# 03_RADIO.net
KiCad netlist of a schematic drawn in Altium Designer
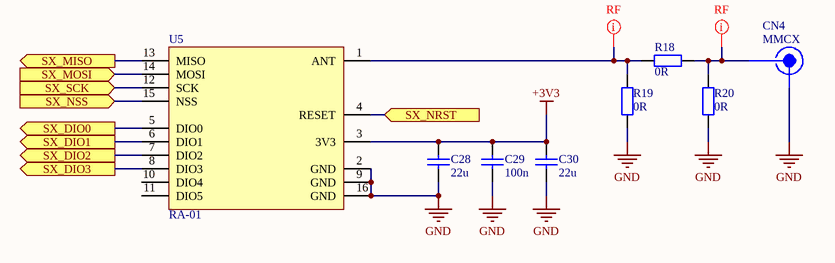
[diagram p0: 03_RADIO.SchDoc]

(export (version "E")
  (design (tool "Eeschema 10.0.6"))
  (components
    (comp (ref "C28")
      (value "22u")
      (footprint "C0805_IPC_MD")
      (description "CAP CER 22UF 16V X5R 0805")
      (fields
        (field (name "MANUFACTURER") "Samsung Electro-Mechanics")
        (field (name "MANUFACTURER PART NUMBER") "CL21A226MOCLRNC")
      )
      (libsource (lib "alfasat_lib") (part "CL21A226MOCLRNC"))
    )
    (comp (ref "C29")
      (value "100n")
      (footprint "C0603_IPC_MD")
      (description "CAP CER 0.1UF 16V X7R 0603")
      (fields
        (field (name "MANUFACTURER") "Samsung Electro-Mechanics")
        (field (name "MANUFACTURER PART NUMBER") "CL10B104KO8WPNC")
      )
      (libsource (lib "alfasat_lib") (part "CL10B104KO8WPNC"))
    )
    (comp (ref "C30")
      (value "22u")
      (footprint "C0805_IPC_MD")
      (description "CAP CER 22UF 16V X5R 0805")
      (fields
        (field (name "MANUFACTURER") "Samsung Electro-Mechanics")
        (field (name "MANUFACTURER PART NUMBER") "CL21A226MOCLRNC")
      )
      (libsource (lib "alfasat_lib") (part "CL21A226MOCLRNC"))
    )
    (comp (ref "CN4")
      (value "MMCX")
      (footprint "MMCX_EDGE")
      (description "MMCX PCB EDGE CONN")
      (fields (field (name "MANUFACTURER") "China"))
      (libsource (lib "alfasat_lib") (part "MMCX"))
    )
    (comp (ref "R18")
      (value "0R")
      (footprint "R0603_IPC_MD")
      (description "RES SMD 0 OHM JUMPER 1/10W 0603")
      (fields
        (field (name "MANUFACTURER") "Bourns Inc.")
        (field (name "MANUFACTURER PART NUMBER") "CR0603-J/-000ELF")
      )
      (libsource (lib "alfasat_parts_lib") (part "CR0603-J/-000ELF"))
    )
    (comp (ref "R19")
      (value "0R")
      (footprint "R0603_IPC_MD")
      (description "RES SMD 0 OHM JUMPER 1/10W 0603")
      (fields
        (field (name "MANUFACTURER") "Bourns Inc.")
        (field (name "MANUFACTURER PART NUMBER") "CR0603-J/-000ELF")
      )
      (libsource (lib "") (part "CR0603-J/-000ELF_1"))
    )
    (comp (ref "R20")
      (value "0R")
      (footprint "R0603_IPC_MD")
      (description "RES SMD 0 OHM JUMPER 1/10W 0603")
      (fields
        (field (name "MANUFACTURER") "Bourns Inc.")
        (field (name "MANUFACTURER PART NUMBER") "CR0603-J/-000ELF")
      )
      (libsource (lib "") (part "CR0603-J/-000ELF_1"))
    )
    (comp (ref "U5")
      (value "RA-01")
      (footprint "RA-01")
      (description "Wireless Modules SX1278")
      (fields (field (name "MANUFACTURER") "Ai-Thinker"))
      (libsource (lib "alfasat_lib") (part "RA-01"))
    )
  )
  (nets
    (net (code "1") (name "+3V3") (class "Default")
      (node (ref "C28") (pin "1") (pinfunction "1_1") (pintype "passive"))
      (node (ref "C29") (pin "1") (pinfunction "1_1") (pintype "passive"))
      (node (ref "C30") (pin "1") (pinfunction "1_1") (pintype "passive"))
      (node (ref "U5") (pin "3") (pinfunction "3V3_3") (pintype "passive"))
    )
    (net (code "2") (name "/SX_DIO0") (class "Default")
      (node (ref "U5") (pin "5") (pinfunction "DIO0_5") (pintype "passive"))
    )
    (net (code "3") (name "/SX_DIO1") (class "Default")
      (node (ref "U5") (pin "6") (pinfunction "DIO1_6") (pintype "passive"))
    )
    (net (code "4") (name "/SX_DIO2") (class "Default")
      (node (ref "U5") (pin "7") (pinfunction "DIO2_7") (pintype "passive"))
    )
    (net (code "5") (name "/SX_DIO3") (class "Default")
      (node (ref "U5") (pin "8") (pinfunction "DIO3_8") (pintype "passive"))
    )
    (net (code "6") (name "/SX_MISO") (class "Default")
      (node (ref "U5") (pin "13") (pinfunction "MISO_13") (pintype "passive"))
    )
    (net (code "7") (name "/SX_MOSI") (class "Default")
      (node (ref "U5") (pin "14") (pinfunction "MOSI_14") (pintype "passive"))
    )
    (net (code "8") (name "/SX_NRST") (class "Default")
      (node (ref "U5") (pin "4") (pinfunction "RESET_4") (pintype "passive"))
    )
    (net (code "9") (name "/SX_NSS") (class "Default")
      (node (ref "U5") (pin "15") (pinfunction "NSS_15") (pintype "passive"))
    )
    (net (code "10") (name "/SX_SCK") (class "Default")
      (node (ref "U5") (pin "12") (pinfunction "SCK_12") (pintype "passive"))
    )
    (net (code "11") (name "GND") (class "Default")
      (node (ref "C28") (pin "2") (pinfunction "2_2") (pintype "passive"))
      (node (ref "C29") (pin "2") (pinfunction "2_2") (pintype "passive"))
      (node (ref "C30") (pin "2") (pinfunction "2_2") (pintype "passive"))
      (node (ref "CN4") (pin "1") (pinfunction "1_1") (pintype "passive"))
      (node (ref "R19") (pin "1") (pinfunction "1_1") (pintype "passive"))
      (node (ref "R20") (pin "1") (pinfunction "1_1") (pintype "passive"))
      (node (ref "U5") (pin "16") (pinfunction "GND_16") (pintype "passive"))
      (node (ref "U5") (pin "2") (pinfunction "GND_2") (pintype "passive"))
      (node (ref "U5") (pin "9") (pinfunction "GND_9") (pintype "passive"))
    )
    (net (code "12") (name "Net-(CN4-Pad2)") (class "Default")
      (node (ref "CN4") (pin "2") (pinfunction "2_2") (pintype "passive"))
      (node (ref "R18") (pin "2") (pinfunction "2_2") (pintype "passive"))
      (node (ref "R20") (pin "2") (pinfunction "2_2") (pintype "passive"))
    )
    (net (code "13") (name "Net-(U5-ANT)") (class "Default")
      (node (ref "R18") (pin "1") (pinfunction "1_1") (pintype "passive"))
      (node (ref "R19") (pin "2") (pinfunction "2_2") (pintype "passive"))
      (node (ref "U5") (pin "1") (pinfunction "ANT_1") (pintype "passive"))
    )
    (net (code "14") (name "unconnected-(U5-DIO4-Pad10)") (class "Default")
      (node (ref "U5") (pin "10") (pinfunction "DIO4_10") (pintype "passive"))
    )
    (net (code "15") (name "unconnected-(U5-DIO5-Pad11)") (class "Default")
      (node (ref "U5") (pin "11") (pinfunction "DIO5_11") (pintype "passive"))
    )
  )
)
